# FE.net
KiCad netlist of a schematic drawn in Altium Designer
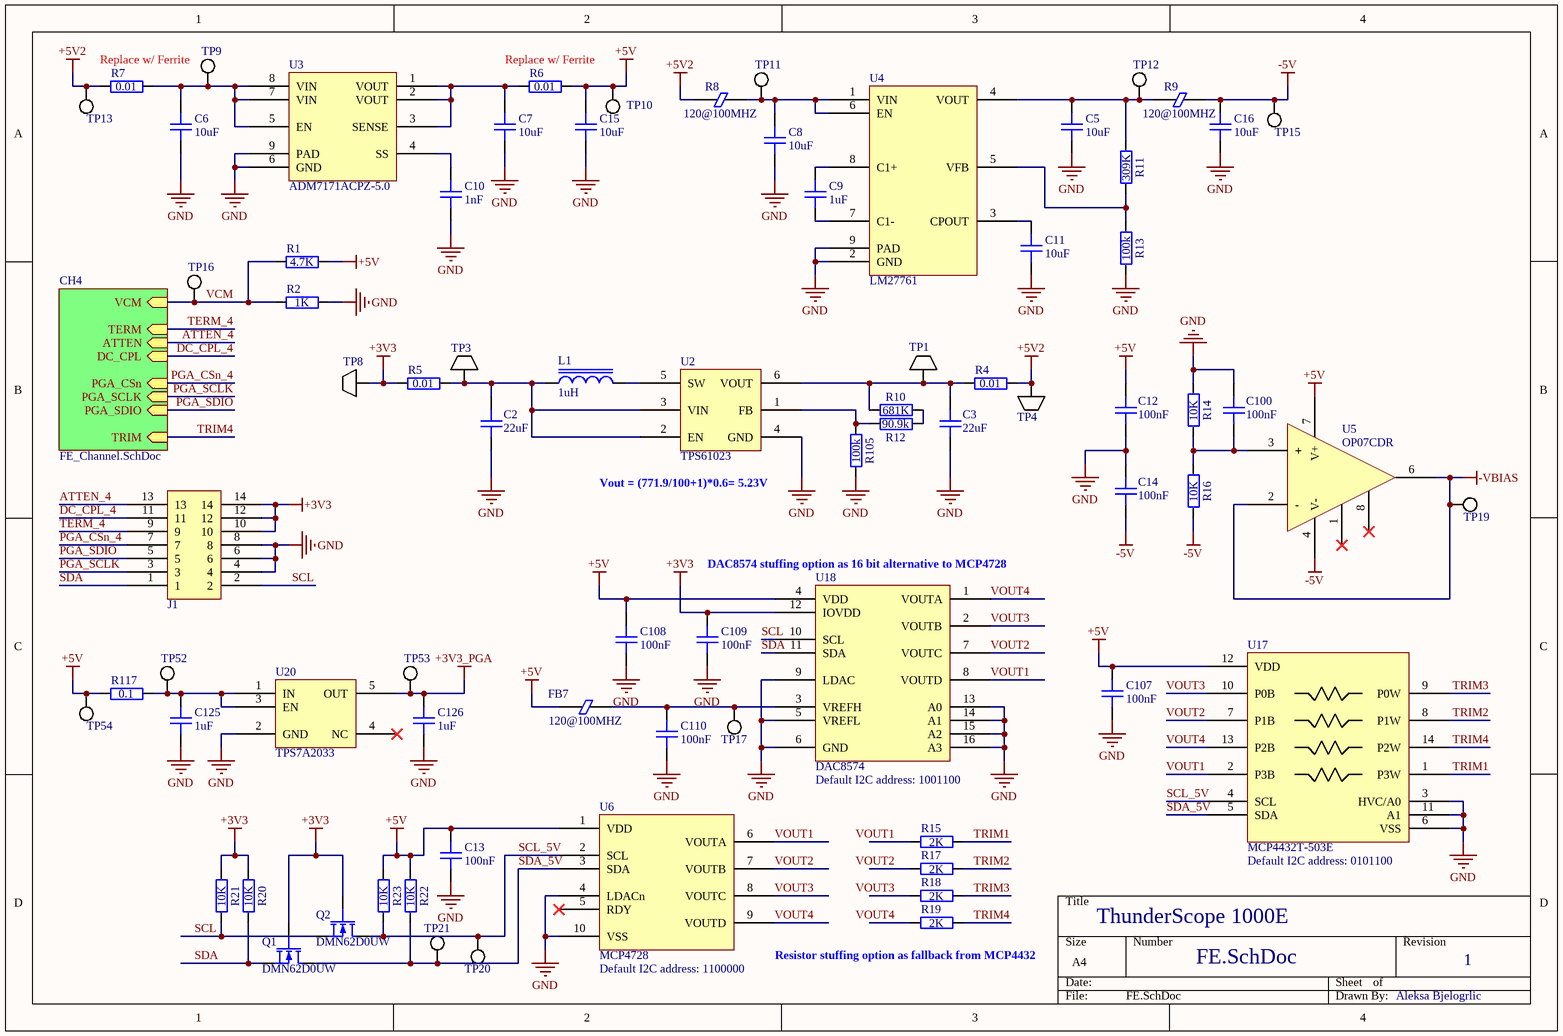
[diagram p0: FE.SchDoc]

(export (version "E")
  (design (tool "Eeschema 10.0.6"))
  (components
    (comp (ref "C2")
      (value "22uF")
      (footprint "GEN_C_0805")
      (libsource (lib "DSO") (part "CAP 22uF 25V X5R 0805"))
    )
    (comp (ref "C3")
      (value "22uF")
      (footprint "GEN_C_0805")
      (libsource (lib "DSO") (part "CAP 22uF 25V X5R 0805"))
    )
    (comp (ref "C5")
      (value "10uF")
      (footprint "GEN_C_0603")
      (libsource (lib "DSO") (part "CAP 10uF 10V X5R 0603"))
    )
    (comp (ref "C6")
      (value "10uF")
      (footprint "GEN_C_0603")
      (libsource (lib "DSO") (part "CAP 10uF 10V X5R 0603"))
    )
    (comp (ref "C7")
      (value "10uF")
      (footprint "GEN_C_0603")
      (libsource (lib "DSO") (part "CAP 10uF 10V X5R 0603"))
    )
    (comp (ref "C8")
      (value "10uF")
      (footprint "GEN_C_0603")
      (libsource (lib "DSO") (part "CAP 10uF 10V X5R 0603"))
    )
    (comp (ref "C9")
      (value "1uF")
      (footprint "GEN_C_0402")
      (libsource (lib "DSO") (part "CAP 1uF 25V X5R 0402"))
    )
    (comp (ref "C10")
      (value "1nF")
      (footprint "GEN_C_0402")
      (libsource (lib "DSO") (part "CAP 1nF 50V C0G 0402"))
    )
    (comp (ref "C11")
      (value "10uF")
      (footprint "GEN_C_0603")
      (libsource (lib "DSO") (part "CAP 10uF 10V X5R 0603"))
    )
    (comp (ref "C12")
      (value "100nF")
      (footprint "GEN_C_0402")
      (libsource (lib "DSO") (part "CAP 100nF 16V X7R 0402"))
    )
    (comp (ref "C13")
      (value "100nF")
      (footprint "GEN_C_0402")
      (libsource (lib "DSO") (part "CAP 100nF 16V X7R 0402"))
    )
    (comp (ref "C14")
      (value "100nF")
      (footprint "GEN_C_0402")
      (libsource (lib "DSO") (part "CAP 100nF 16V X7R 0402"))
    )
    (comp (ref "C15")
      (value "10uF")
      (footprint "GEN_C_0603")
      (libsource (lib "DSO") (part "CAP 10uF 10V X5R 0603"))
    )
    (comp (ref "C16")
      (value "10uF")
      (footprint "GEN_C_0603")
      (libsource (lib "DSO") (part "CAP 10uF 10V X5R 0603"))
    )
    (comp (ref "C100")
      (value "100nF")
      (footprint "GEN_C_0402")
      (libsource (lib "DSO") (part "CAP 100nF 16V X7R 0402"))
    )
    (comp (ref "C107")
      (value "100nF")
      (footprint "GEN_C_0402")
      (libsource (lib "DSO") (part "CAP 100nF 16V X7R 0402"))
    )
    (comp (ref "C108")
      (value "100nF")
      (footprint "GEN_C_0402")
      (libsource (lib "DSO") (part "CAP 100nF 16V X7R 0402"))
    )
    (comp (ref "C109")
      (value "100nF")
      (footprint "GEN_C_0402")
      (libsource (lib "DSO") (part "CAP 100nF 16V X7R 0402"))
    )
    (comp (ref "C110")
      (value "100nF")
      (footprint "GEN_C_0402")
      (libsource (lib "DSO") (part "CAP 100nF 16V X7R 0402"))
    )
    (comp (ref "C125")
      (value "1uF")
      (footprint "GEN_C_0402")
      (libsource (lib "DSO") (part "CAP 1uF 25V X5R 0402"))
    )
    (comp (ref "C126")
      (value "1uF")
      (footprint "GEN_C_0402")
      (libsource (lib "DSO") (part "CAP 1uF 25V X5R 0402"))
    )
    (comp (ref "FB7")
      (value "120@100MHZ")
      (footprint "GEN_R_0402")
      (libsource (lib "DSO") (part "FERRITE BEAD 120 OHM 0402"))
    )
    (comp (ref "J1")
      (value "2.54mm 2X7 Pin TH")
      (footprint "GEN_2.54mm_2X7_Pin_TH_RA")
      (libsource (lib "DSO") (part "CONN 2.54mm 2X7 Pin TH RA"))
    )
    (comp (ref "L1")
      (value "1uH")
      (footprint "GEN_L_1210")
      (libsource (lib "DSO") (part "IND 1uH 3.1A 45 MOHM 1210"))
    )
    (comp (ref "Q1")
      (value "DMN62D0UW")
      (footprint "GEN_SOT_323")
      (libsource (lib "DSO") (part "NMOS DMN62D0UW"))
    )
    (comp (ref "Q2")
      (value "DMN62D0UW")
      (footprint "GEN_SOT_323")
      (libsource (lib "DSO") (part "NMOS DMN62D0UW"))
    )
    (comp (ref "R1")
      (value "4.7K")
      (footprint "GEN_R_0402")
      (fields
        (field (name "TOLERANCE") "1%")
        (field (name "MANUFACTURER") "Panasonic")
        (field (name "MANUFACTURER PART NUMBER") "ERJ-2RKF4701X")
      )
      (libsource (lib "DSO") (part "RES 4.7K OHM 1% 1/10W 0402"))
    )
    (comp (ref "R2")
      (value "1K")
      (footprint "GEN_R_0402")
      (fields
        (field (name "TOLERANCE") "1%")
        (field (name "MANUFACTURER") "Yageo")
        (field (name "HOUSE PART NUMBER") "R-1K-0402-1%-001")
      )
      (libsource (lib "DSO") (part "RES 1K OHM 1% 1/10W 0402"))
    )
    (comp (ref "R4")
      (value "0.01")
      (footprint "GEN_R_0603")
      (fields (field (name "TOLERANCE") "1%"))
      (libsource (lib "DSO") (part "RES 0.01 OHM 1% 1/4W 0603"))
    )
    (comp (ref "R5")
      (value "0.01")
      (footprint "GEN_R_0603")
      (fields (field (name "TOLERANCE") "1%"))
      (libsource (lib "") (part "RES 0.01 OHM 1% 1/4W 0603_1"))
    )
    (comp (ref "R6")
      (value "0.01")
      (footprint "GEN_R_0603")
      (fields (field (name "TOLERANCE") "1%"))
      (libsource (lib "DSO") (part "RES 0.01 OHM 1% 1/4W 0603"))
    )
    (comp (ref "R7")
      (value "0.01")
      (footprint "GEN_R_0603")
      (fields (field (name "TOLERANCE") "1%"))
      (libsource (lib "DSO") (part "RES 0.01 OHM 1% 1/4W 0603"))
    )
    (comp (ref "R8")
      (value "120@100MHZ")
      (footprint "GEN_R_0402")
      (fields (field (name "MANUFACTURER") "Murata") (field (name "HOUSE PART NUMBER") "BLM15PX121SN1D"))
      (libsource (lib "DSO") (part "FERRITE BEAD 120 OHM 0402"))
    )
    (comp (ref "R9")
      (value "120@100MHZ")
      (footprint "GEN_R_0402")
      (fields (field (name "MANUFACTURER") "Murata") (field (name "HOUSE PART NUMBER") "BLM15PX121SN1D"))
      (libsource (lib "DSO") (part "FERRITE BEAD 120 OHM 0402"))
    )
    (comp (ref "R10")
      (value "681K")
      (footprint "GEN_R_0402")
      (fields (field (name "TOLERANCE") "1%"))
      (libsource (lib "DSO") (part "RES 681K OHM 1% 1/16W 0402"))
    )
    (comp (ref "R11")
      (value "309K")
      (footprint "GEN_R_0402")
      (fields (field (name "TOLERANCE") "1%"))
      (libsource (lib "DSO") (part "RES 309K OHM 1% 1/16W 0402"))
    )
    (comp (ref "R12")
      (value "90.9k")
      (footprint "GEN_R_0402")
      (fields (field (name "TOLERANCE") "1%"))
      (libsource (lib "DSO") (part "RES 90.9K OHM 1% 1/16W 0402"))
    )
    (comp (ref "R13")
      (value "100k")
      (footprint "GEN_R_0402")
      (fields (field (name "TOLERANCE") "1%"))
      (libsource (lib "DSO") (part "RES 100K OHM 1% 1/10W 0402"))
    )
    (comp (ref "R14")
      (value "10K")
      (footprint "GEN_R_0402")
      (fields (field (name "TOLERANCE") "1%"))
      (libsource (lib "DSO") (part "RES 10K OHM 1% 1/10W 0402"))
    )
    (comp (ref "R15")
      (value "2K")
      (footprint "GEN_R_0402")
      (fields (field (name "TOLERANCE") "1%"))
      (libsource (lib "DSO") (part "RES 2K OHM 1% 1/16W 0402"))
    )
    (comp (ref "R16")
      (value "10K")
      (footprint "GEN_R_0402")
      (fields (field (name "TOLERANCE") "1%"))
      (libsource (lib "DSO") (part "RES 10K OHM 1% 1/10W 0402"))
    )
    (comp (ref "R17")
      (value "2K")
      (footprint "GEN_R_0402")
      (fields (field (name "TOLERANCE") "1%"))
      (libsource (lib "DSO") (part "RES 2K OHM 1% 1/16W 0402"))
    )
    (comp (ref "R18")
      (value "2K")
      (footprint "GEN_R_0402")
      (fields (field (name "TOLERANCE") "1%"))
      (libsource (lib "DSO") (part "RES 2K OHM 1% 1/16W 0402"))
    )
    (comp (ref "R19")
      (value "2K")
      (footprint "GEN_R_0402")
      (fields (field (name "TOLERANCE") "1%"))
      (libsource (lib "DSO") (part "RES 2K OHM 1% 1/16W 0402"))
    )
    (comp (ref "R20")
      (value "10K")
      (footprint "GEN_R_0402")
      (fields (field (name "TOLERANCE") "1%"))
      (libsource (lib "DSO") (part "RES 10K OHM 1% 1/10W 0402"))
    )
    (comp (ref "R21")
      (value "10K")
      (footprint "GEN_R_0402")
      (fields (field (name "TOLERANCE") "1%"))
      (libsource (lib "DSO") (part "RES 10K OHM 1% 1/10W 0402"))
    )
    (comp (ref "R22")
      (value "10K")
      (footprint "GEN_R_0402")
      (fields (field (name "TOLERANCE") "1%"))
      (libsource (lib "DSO") (part "RES 10K OHM 1% 1/10W 0402"))
    )
    (comp (ref "R23")
      (value "10K")
      (footprint "GEN_R_0402")
      (fields (field (name "TOLERANCE") "1%"))
      (libsource (lib "DSO") (part "RES 10K OHM 1% 1/10W 0402"))
    )
    (comp (ref "R105")
      (value "100k")
      (footprint "GEN_R_0402")
      (fields (field (name "TOLERANCE") "1%"))
      (libsource (lib "DSO") (part "RES 100K OHM 1% 1/10W 0402"))
    )
    (comp (ref "R117")
      (value "0.1")
      (footprint "GEN_R_0402")
      (fields (field (name "TOLERANCE") "1%"))
      (libsource (lib "DSO") (part "RES 0.1 OHM 1% 1/6W 0402"))
    )
    (comp (ref "TP1") (value "5015") (footprint "KEY_5015") (libsource (lib "DSO") (part "TP KEYSTONE 5015")))
    (comp (ref "TP3") (value "5015") (footprint "KEY_5015") (libsource (lib "DSO") (part "TP KEYSTONE 5015")))
    (comp (ref "TP4") (value "5015") (footprint "KEY_5015") (libsource (lib "DSO") (part "TP KEYSTONE 5015")))
    (comp (ref "TP8") (value "5015") (footprint "KEY_5015") (libsource (lib "DSO") (part "TP KEYSTONE 5015")))
    (comp (ref "TP9") (value "PCB") (footprint "GEN_TP_PCB") (libsource (lib "DSO") (part "TP PCB 1mm")))
    (comp (ref "TP10") (value "PCB") (footprint "GEN_TP_PCB") (libsource (lib "DSO") (part "TP PCB 1mm")))
    (comp (ref "TP11") (value "PCB") (footprint "GEN_TP_PCB") (libsource (lib "DSO") (part "TP PCB 1mm")))
    (comp (ref "TP12") (value "PCB") (footprint "GEN_TP_PCB") (libsource (lib "DSO") (part "TP PCB 1mm")))
    (comp (ref "TP13") (value "PCB") (footprint "GEN_TP_PCB") (libsource (lib "DSO") (part "TP PCB 1mm")))
    (comp (ref "TP15") (value "PCB") (footprint "GEN_TP_PCB") (libsource (lib "DSO") (part "TP PCB 1mm")))
    (comp (ref "TP16") (value "PCB") (footprint "GEN_TP_PCB") (libsource (lib "DSO") (part "TP PCB 1mm")))
    (comp (ref "TP17") (value "PCB") (footprint "GEN_TP_PCB") (libsource (lib "DSO") (part "TP PCB 1mm")))
    (comp (ref "TP19") (value "PCB") (footprint "GEN_TP_PCB") (libsource (lib "DSO") (part "TP PCB 1mm")))
    (comp (ref "TP20") (value "PCB") (footprint "GEN_TP_PCB") (libsource (lib "DSO") (part "TP PCB 1mm")))
    (comp (ref "TP21") (value "PCB") (footprint "GEN_TP_PCB") (libsource (lib "DSO") (part "TP PCB 1mm")))
    (comp (ref "TP52") (value "PCB") (footprint "GEN_TP_PCB") (libsource (lib "DSO") (part "TP PCB 1mm")))
    (comp (ref "TP53") (value "PCB") (footprint "GEN_TP_PCB") (libsource (lib "DSO") (part "TP PCB 1mm")))
    (comp (ref "TP54") (value "PCB") (footprint "GEN_TP_PCB") (libsource (lib "DSO") (part "TP PCB 1mm")))
    (comp (ref "U2")
      (value "TPS61023")
      (footprint "TI_SOT563_DRL0006A")
      (libsource (lib "DSO") (part "IC BOOST TPS61023"))
    )
    (comp (ref "U3")
      (value "ADM7171ACPZ-5.0")
      (footprint "AD_DFN8_CP-8-21")
      (libsource (lib "DSO") (part "IC LDO ADM7171ACPZ-5.0"))
    )
    (comp (ref "U4")
      (value "LM27761")
      (footprint "TI_WSON8_DSG0008A")
      (libsource (lib "DSO") (part "IC CPUMP LM27761"))
    )
    (comp (ref "U5")
      (value "OP07CDR")
      (footprint "TI_SOIC8_D0008A")
      (libsource (lib "DSO") (part "IC OPAMP OP07CDR"))
    )
    (comp (ref "U6")
      (value "MCP4728")
      (footprint "MC_MSOP10_UN")
      (libsource (lib "DSO") (part "IC DAC QUAD MCP4728"))
    )
    (comp (ref "U17")
      (value "MCP4432T-503E")
      (footprint "MC_TSSOP14")
      (libsource (lib "DSO") (part "IC DIGIPOT QUAD MCP4432T-503E"))
    )
    (comp (ref "U18")
      (value "DAC8574")
      (footprint "TI_TSSOP16_PW0016A")
      (libsource (lib "DSO") (part "IC DAC QUAD DAC8574"))
    )
    (comp (ref "U20")
      (value "TPS7A2033")
      (footprint "GEN_SOT23_5_950_2900X1600X1450")
      (fields
        (field (name "MANUFACTURER") "Texas Instruments")
        (field (name "MANUFACTURER PART NUMBER") "TPS7A2033PDBVR")
      )
      (libsource (lib "DSO") (part "IC LDO TPS7A2033"))
    )
  )
  (nets
    (net (code "1") (name "+3V3") (class "Default")
      (node (ref "C109") (pin "2") (pinfunction "2_2") (pintype "passive"))
      (node (ref "J1") (pin "10") (pinfunction "10_10") (pintype "passive"))
      (node (ref "J1") (pin "12") (pinfunction "12_12") (pintype "passive"))
      (node (ref "J1") (pin "14") (pinfunction "14_14") (pintype "passive"))
      (node (ref "Q1") (pin "2") (pinfunction "G_2") (pintype "passive"))
      (node (ref "Q2") (pin "2") (pinfunction "G_2") (pintype "passive"))
      (node (ref "R20") (pin "2") (pinfunction "2_2") (pintype "passive"))
      (node (ref "R21") (pin "2") (pinfunction "2_2") (pintype "passive"))
      (node (ref "R5") (pin "2") (pinfunction "2_2") (pintype "passive"))
      (node (ref "TP8") (pin "1") (pinfunction "1_1") (pintype "passive"))
      (node (ref "U18") (pin "12") (pinfunction "IOVDD_12") (pintype "power_in"))
    )
    (net (code "2") (name "+3V3_PGA") (class "Default")
      (node (ref "C126") (pin "2") (pinfunction "2_2") (pintype "passive"))
      (node (ref "TP53") (pin "1") (pinfunction "1_1") (pintype "passive"))
      (node (ref "U20") (pin "5") (pinfunction "OUT_5") (pintype "power_in"))
    )
    (net (code "3") (name "+5V") (class "Default")
      (node (ref "C107") (pin "2") (pinfunction "2_2") (pintype "passive"))
      (node (ref "C108") (pin "2") (pinfunction "2_2") (pintype "passive"))
      (node (ref "C12") (pin "1") (pinfunction "1_1") (pintype "passive"))
      (node (ref "C13") (pin "2") (pinfunction "2_2") (pintype "passive"))
      (node (ref "C15") (pin "2") (pinfunction "2_2") (pintype "passive"))
      (node (ref "FB7") (pin "2") (pinfunction "2_2") (pintype "passive"))
      (node (ref "R1") (pin "2") (pinfunction "2_2") (pintype "passive"))
      (node (ref "R117") (pin "1") (pinfunction "1_1") (pintype "passive"))
      (node (ref "R22") (pin "2") (pinfunction "2_2") (pintype "passive"))
      (node (ref "R23") (pin "2") (pinfunction "2_2") (pintype "passive"))
      (node (ref "R6") (pin "2") (pinfunction "2_2") (pintype "passive"))
      (node (ref "TP10") (pin "1") (pinfunction "1_1") (pintype "passive"))
      (node (ref "TP54") (pin "1") (pinfunction "1_1") (pintype "passive"))
      (node (ref "U17") (pin "12") (pinfunction "VDD_12") (pintype "power_in"))
      (node (ref "U18") (pin "4") (pinfunction "VDD_4") (pintype "power_in"))
      (node (ref "U5") (pin "7") (pinfunction "V+_7") (pintype "passive"))
      (node (ref "U6") (pin "1") (pinfunction "VDD_1") (pintype "power_in"))
    )
    (net (code "4") (name "+5V2") (class "Default")
      (node (ref "R4") (pin "2") (pinfunction "2_2") (pintype "passive"))
      (node (ref "R7") (pin "1") (pinfunction "1_1") (pintype "passive"))
      (node (ref "R8") (pin "1") (pinfunction "1_1") (pintype "passive"))
      (node (ref "TP13") (pin "1") (pinfunction "1_1") (pintype "passive"))
      (node (ref "TP4") (pin "1") (pinfunction "1_1") (pintype "passive"))
    )
    (net (code "5") (name "-5V") (class "Default")
      (node (ref "C14") (pin "2") (pinfunction "2_2") (pintype "passive"))
      (node (ref "C16") (pin "2") (pinfunction "2_2") (pintype "passive"))
      (node (ref "R16") (pin "1") (pinfunction "1_1") (pintype "passive"))
      (node (ref "R9") (pin "2") (pinfunction "2_2") (pintype "passive"))
      (node (ref "TP15") (pin "1") (pinfunction "1_1") (pintype "passive"))
      (node (ref "U5") (pin "4") (pinfunction "V-_4") (pintype "passive"))
    )
    (net (code "6") (name "-VBIAS") (class "Default")
      (node (ref "TP19") (pin "1") (pinfunction "1_1") (pintype "passive"))
      (node (ref "U5") (pin "2") (pinfunction "-_2") (pintype "passive"))
      (node (ref "U5") (pin "6") (pinfunction "OUT_6") (pintype "passive"))
    )
    (net (code "7") (name "/ATTEN_4") (class "Default")
      (node (ref "J1") (pin "13") (pinfunction "13_13") (pintype "passive"))
    )
    (net (code "8") (name "/DC_CPL_4") (class "Default")
      (node (ref "J1") (pin "11") (pinfunction "11_11") (pintype "passive"))
    )
    (net (code "9") (name "/PGA_CSn_4") (class "Default")
      (node (ref "J1") (pin "7") (pinfunction "7_7") (pintype "passive"))
    )
    (net (code "10") (name "/PGA_SCLK") (class "Default")
      (node (ref "J1") (pin "3") (pinfunction "3_3") (pintype "passive"))
    )
    (net (code "11") (name "/PGA_SDIO") (class "Default")
      (node (ref "J1") (pin "5") (pinfunction "5_5") (pintype "passive"))
    )
    (net (code "12") (name "/SCL") (class "Default")
      (node (ref "J1") (pin "2") (pinfunction "2_2") (pintype "passive"))
      (node (ref "Q2") (pin "3") (pinfunction "S_3") (pintype "passive"))
      (node (ref "R21") (pin "1") (pinfunction "1_1") (pintype "passive"))
      (node (ref "U18") (pin "10") (pinfunction "SCL_10") (pintype "passive"))
    )
    (net (code "13") (name "/SCL_5V") (class "Default")
      (node (ref "Q2") (pin "1") (pinfunction "D_1") (pintype "passive"))
      (node (ref "R23") (pin "1") (pinfunction "1_1") (pintype "passive"))
      (node (ref "TP20") (pin "1") (pinfunction "1_1") (pintype "passive"))
      (node (ref "U17") (pin "4") (pinfunction "SCL_4") (pintype "passive"))
      (node (ref "U6") (pin "2") (pinfunction "SCL_2") (pintype "passive"))
    )
    (net (code "14") (name "/SDA") (class "Default")
      (node (ref "J1") (pin "1") (pinfunction "1_1") (pintype "passive"))
      (node (ref "Q1") (pin "3") (pinfunction "S_3") (pintype "passive"))
      (node (ref "R20") (pin "1") (pinfunction "1_1") (pintype "passive"))
      (node (ref "U18") (pin "11") (pinfunction "SDA_11") (pintype "passive"))
    )
    (net (code "15") (name "/SDA_5V") (class "Default")
      (node (ref "Q1") (pin "1") (pinfunction "D_1") (pintype "passive"))
      (node (ref "R22") (pin "1") (pinfunction "1_1") (pintype "passive"))
      (node (ref "TP21") (pin "1") (pinfunction "1_1") (pintype "passive"))
      (node (ref "U17") (pin "5") (pinfunction "SDA_5") (pintype "passive"))
      (node (ref "U6") (pin "3") (pinfunction "SDA_3") (pintype "passive"))
    )
    (net (code "16") (name "/TERM_4") (class "Default")
      (node (ref "J1") (pin "9") (pinfunction "9_9") (pintype "passive"))
    )
    (net (code "17") (name "/TRIM1") (class "Default")
      (node (ref "R15") (pin "1") (pinfunction "1_1") (pintype "passive"))
      (node (ref "U17") (pin "1") (pinfunction "P3W_1") (pintype "passive"))
    )
    (net (code "18") (name "/TRIM2") (class "Default")
      (node (ref "R17") (pin "1") (pinfunction "1_1") (pintype "passive"))
      (node (ref "U17") (pin "8") (pinfunction "P1W_8") (pintype "passive"))
    )
    (net (code "19") (name "/TRIM3") (class "Default")
      (node (ref "R18") (pin "1") (pinfunction "1_1") (pintype "passive"))
      (node (ref "U17") (pin "9") (pinfunction "P0W_9") (pintype "passive"))
    )
    (net (code "20") (name "/TRIM4") (class "Default")
      (node (ref "R19") (pin "1") (pinfunction "1_1") (pintype "passive"))
      (node (ref "U17") (pin "14") (pinfunction "P2W_14") (pintype "passive"))
    )
    (net (code "21") (name "/VCM") (class "Default")
      (node (ref "R1") (pin "1") (pinfunction "1_1") (pintype "passive"))
      (node (ref "R2") (pin "1") (pinfunction "1_1") (pintype "passive"))
      (node (ref "TP16") (pin "1") (pinfunction "1_1") (pintype "passive"))
    )
    (net (code "22") (name "/VOUT1") (class "Default")
      (node (ref "R15") (pin "2") (pinfunction "2_2") (pintype "passive"))
      (node (ref "U17") (pin "2") (pinfunction "P3B_2") (pintype "passive"))
      (node (ref "U18") (pin "8") (pinfunction "VOUTD_8") (pintype "passive"))
      (node (ref "U6") (pin "6") (pinfunction "VOUTA_6") (pintype "passive"))
    )
    (net (code "23") (name "/VOUT2") (class "Default")
      (node (ref "R17") (pin "2") (pinfunction "2_2") (pintype "passive"))
      (node (ref "U17") (pin "7") (pinfunction "P1B_7") (pintype "passive"))
      (node (ref "U18") (pin "7") (pinfunction "VOUTC_7") (pintype "passive"))
      (node (ref "U6") (pin "7") (pinfunction "VOUTB_7") (pintype "passive"))
    )
    (net (code "24") (name "/VOUT3") (class "Default")
      (node (ref "R18") (pin "2") (pinfunction "2_2") (pintype "passive"))
      (node (ref "U17") (pin "10") (pinfunction "P0B_10") (pintype "passive"))
      (node (ref "U18") (pin "2") (pinfunction "VOUTB_2") (pintype "passive"))
      (node (ref "U6") (pin "8") (pinfunction "VOUTC_8") (pintype "passive"))
    )
    (net (code "25") (name "/VOUT4") (class "Default")
      (node (ref "R19") (pin "2") (pinfunction "2_2") (pintype "passive"))
      (node (ref "U17") (pin "13") (pinfunction "P2B_13") (pintype "passive"))
      (node (ref "U18") (pin "1") (pinfunction "VOUTA_1") (pintype "passive"))
      (node (ref "U6") (pin "9") (pinfunction "VOUTD_9") (pintype "passive"))
    )
    (net (code "26") (name "GND") (class "Default")
      (node (ref "C10") (pin "1") (pinfunction "1_1") (pintype "passive"))
      (node (ref "C100") (pin "1") (pinfunction "1_1") (pintype "passive"))
      (node (ref "C107") (pin "1") (pinfunction "1_1") (pintype "passive"))
      (node (ref "C108") (pin "1") (pinfunction "1_1") (pintype "passive"))
      (node (ref "C109") (pin "1") (pinfunction "1_1") (pintype "passive"))
      (node (ref "C11") (pin "1") (pinfunction "1_1") (pintype "passive"))
      (node (ref "C110") (pin "1") (pinfunction "1_1") (pintype "passive"))
      (node (ref "C12") (pin "2") (pinfunction "2_2") (pintype "passive"))
      (node (ref "C125") (pin "1") (pinfunction "1_1") (pintype "passive"))
      (node (ref "C126") (pin "1") (pinfunction "1_1") (pintype "passive"))
      (node (ref "C13") (pin "1") (pinfunction "1_1") (pintype "passive"))
      (node (ref "C14") (pin "1") (pinfunction "1_1") (pintype "passive"))
      (node (ref "C15") (pin "1") (pinfunction "1_1") (pintype "passive"))
      (node (ref "C16") (pin "1") (pinfunction "1_1") (pintype "passive"))
      (node (ref "C2") (pin "1") (pinfunction "1_1") (pintype "passive"))
      (node (ref "C3") (pin "1") (pinfunction "1_1") (pintype "passive"))
      (node (ref "C5") (pin "1") (pinfunction "1_1") (pintype "passive"))
      (node (ref "C6") (pin "1") (pinfunction "1_1") (pintype "passive"))
      (node (ref "C7") (pin "1") (pinfunction "1_1") (pintype "passive"))
      (node (ref "C8") (pin "1") (pinfunction "1_1") (pintype "passive"))
      (node (ref "J1") (pin "4") (pinfunction "4_4") (pintype "passive"))
      (node (ref "J1") (pin "6") (pinfunction "6_6") (pintype "passive"))
      (node (ref "J1") (pin "8") (pinfunction "8_8") (pintype "passive"))
      (node (ref "R105") (pin "1") (pinfunction "1_1") (pintype "passive"))
      (node (ref "R13") (pin "1") (pinfunction "1_1") (pintype "passive"))
      (node (ref "R14") (pin "2") (pinfunction "2_2") (pintype "passive"))
      (node (ref "R2") (pin "2") (pinfunction "2_2") (pintype "passive"))
      (node (ref "U17") (pin "11") (pinfunction "A1_11") (pintype "passive"))
      (node (ref "U17") (pin "3") (pinfunction "HVC/A0_3") (pintype "passive"))
      (node (ref "U17") (pin "6") (pinfunction "VSS_6") (pintype "power_in"))
      (node (ref "U18") (pin "13") (pinfunction "A0_13") (pintype "passive"))
      (node (ref "U18") (pin "14") (pinfunction "A1_14") (pintype "passive"))
      (node (ref "U18") (pin "15") (pinfunction "A2_15") (pintype "passive"))
      (node (ref "U18") (pin "16") (pinfunction "A3_16") (pintype "passive"))
      (node (ref "U18") (pin "5") (pinfunction "VREFL_5") (pintype "passive"))
      (node (ref "U18") (pin "6") (pinfunction "GND_6") (pintype "power_in"))
      (node (ref "U18") (pin "9") (pinfunction "LDAC_9") (pintype "passive"))
      (node (ref "U2") (pin "4") (pinfunction "GND_4") (pintype "power_in"))
      (node (ref "U20") (pin "2") (pinfunction "GND_2") (pintype "power_in"))
      (node (ref "U3") (pin "6") (pinfunction "GND_6") (pintype "power_in"))
      (node (ref "U3") (pin "9") (pinfunction "PAD_9") (pintype "passive"))
      (node (ref "U4") (pin "2") (pinfunction "GND_2") (pintype "power_in"))
      (node (ref "U4") (pin "9") (pinfunction "PAD_9") (pintype "power_in"))
      (node (ref "U6") (pin "10") (pinfunction "VSS_10") (pintype "power_in"))
      (node (ref "U6") (pin "4") (pinfunction "LDACn_4") (pintype "passive"))
    )
    (net (code "27") (name "Net-(R10-Pad1)") (class "Default")
      (node (ref "R10") (pin "1") (pinfunction "1_1") (pintype "passive"))
      (node (ref "R12") (pin "2") (pinfunction "2_2") (pintype "passive"))
    )
    (net (code "28") (name "Net-(U2-EN)") (class "Default")
      (node (ref "C2") (pin "2") (pinfunction "2_2") (pintype "passive"))
      (node (ref "L1") (pin "1") (pinfunction "1_1") (pintype "passive"))
      (node (ref "R5") (pin "1") (pinfunction "1_1") (pintype "passive"))
      (node (ref "TP3") (pin "1") (pinfunction "1_1") (pintype "passive"))
      (node (ref "U2") (pin "2") (pinfunction "EN_2") (pintype "passive"))
      (node (ref "U2") (pin "3") (pinfunction "VIN_3") (pintype "power_in"))
    )
    (net (code "29") (name "Net-(U2-FB)") (class "Default")
      (node (ref "R105") (pin "2") (pinfunction "2_2") (pintype "passive"))
      (node (ref "R12") (pin "1") (pinfunction "1_1") (pintype "passive"))
      (node (ref "U2") (pin "1") (pinfunction "FB_1") (pintype "passive"))
    )
    (net (code "30") (name "Net-(U2-SW)") (class "Default")
      (node (ref "L1") (pin "2") (pinfunction "2_2") (pintype "passive"))
      (node (ref "U2") (pin "5") (pinfunction "SW_5") (pintype "passive"))
    )
    (net (code "31") (name "Net-(U2-VOUT)") (class "Default")
      (node (ref "C3") (pin "2") (pinfunction "2_2") (pintype "passive"))
      (node (ref "R10") (pin "2") (pinfunction "2_2") (pintype "passive"))
      (node (ref "R4") (pin "1") (pinfunction "1_1") (pintype "passive"))
      (node (ref "TP1") (pin "1") (pinfunction "1_1") (pintype "passive"))
      (node (ref "U2") (pin "6") (pinfunction "VOUT_6") (pintype "passive"))
    )
    (net (code "32") (name "Net-(U3-EN)") (class "Default")
      (node (ref "C6") (pin "2") (pinfunction "2_2") (pintype "passive"))
      (node (ref "R7") (pin "2") (pinfunction "2_2") (pintype "passive"))
      (node (ref "TP9") (pin "1") (pinfunction "1_1") (pintype "passive"))
      (node (ref "U3") (pin "5") (pinfunction "EN_5") (pintype "passive"))
      (node (ref "U3") (pin "7") (pinfunction "VIN_7") (pintype "power_in"))
      (node (ref "U3") (pin "8") (pinfunction "VIN_8") (pintype "power_in"))
    )
    (net (code "33") (name "Net-(U3-SENSE)") (class "Default")
      (node (ref "C7") (pin "2") (pinfunction "2_2") (pintype "passive"))
      (node (ref "R6") (pin "1") (pinfunction "1_1") (pintype "passive"))
      (node (ref "U3") (pin "1") (pinfunction "VOUT_1") (pintype "power_in"))
      (node (ref "U3") (pin "2") (pinfunction "VOUT_2") (pintype "power_in"))
      (node (ref "U3") (pin "3") (pinfunction "SENSE_3") (pintype "passive"))
    )
    (net (code "34") (name "Net-(U3-SS)") (class "Default")
      (node (ref "C10") (pin "2") (pinfunction "2_2") (pintype "passive"))
      (node (ref "U3") (pin "4") (pinfunction "SS_4") (pintype "passive"))
    )
    (net (code "35") (name "Net-(U4-C1+)") (class "Default")
      (node (ref "C9") (pin "2") (pinfunction "2_2") (pintype "passive"))
      (node (ref "U4") (pin "8") (pinfunction "C1+_8") (pintype "passive"))
    )
    (net (code "36") (name "Net-(U4-C1-)") (class "Default")
      (node (ref "C9") (pin "1") (pinfunction "1_1") (pintype "passive"))
      (node (ref "U4") (pin "7") (pinfunction "C1-_7") (pintype "passive"))
    )
    (net (code "37") (name "Net-(U4-CPOUT)") (class "Default")
      (node (ref "C11") (pin "2") (pinfunction "2_2") (pintype "passive"))
      (node (ref "U4") (pin "3") (pinfunction "CPOUT_3") (pintype "passive"))
    )
    (net (code "38") (name "Net-(U4-EN)") (class "Default")
      (node (ref "C8") (pin "2") (pinfunction "2_2") (pintype "passive"))
      (node (ref "R8") (pin "2") (pinfunction "2_2") (pintype "passive"))
      (node (ref "TP11") (pin "1") (pinfunction "1_1") (pintype "passive"))
      (node (ref "U4") (pin "1") (pinfunction "VIN_1") (pintype "power_in"))
      (node (ref "U4") (pin "6") (pinfunction "EN_6") (pintype "passive"))
    )
    (net (code "39") (name "Net-(U4-VFB)") (class "Default")
      (node (ref "R11") (pin "1") (pinfunction "1_1") (pintype "passive"))
      (node (ref "R13") (pin "2") (pinfunction "2_2") (pintype "passive"))
      (node (ref "U4") (pin "5") (pinfunction "VFB_5") (pintype "passive"))
    )
    (net (code "40") (name "Net-(U4-VOUT)") (class "Default")
      (node (ref "C5") (pin "2") (pinfunction "2_2") (pintype "passive"))
      (node (ref "R11") (pin "2") (pinfunction "2_2") (pintype "passive"))
      (node (ref "R9") (pin "1") (pinfunction "1_1") (pintype "passive"))
      (node (ref "TP12") (pin "1") (pinfunction "1_1") (pintype "passive"))
      (node (ref "U4") (pin "4") (pinfunction "VOUT_4") (pintype "power_in"))
    )
    (net (code "41") (name "Net-(U5-+)") (class "Default")
      (node (ref "C100") (pin "2") (pinfunction "2_2") (pintype "passive"))
      (node (ref "R14") (pin "1") (pinfunction "1_1") (pintype "passive"))
      (node (ref "R16") (pin "2") (pinfunction "2_2") (pintype "passive"))
      (node (ref "U5") (pin "3") (pinfunction "+_3") (pintype "passive"))
    )
    (net (code "42") (name "Net-(U18-VREFH)") (class "Default")
      (node (ref "C110") (pin "2") (pinfunction "2_2") (pintype "passive"))
      (node (ref "FB7") (pin "1") (pinfunction "1_1") (pintype "passive"))
      (node (ref "TP17") (pin "1") (pinfunction "1_1") (pintype "passive"))
      (node (ref "U18") (pin "3") (pinfunction "VREFH_3") (pintype "passive"))
    )
    (net (code "43") (name "Net-(U20-EN)") (class "Default")
      (node (ref "C125") (pin "2") (pinfunction "2_2") (pintype "passive"))
      (node (ref "R117") (pin "2") (pinfunction "2_2") (pintype "passive"))
      (node (ref "TP52") (pin "1") (pinfunction "1_1") (pintype "passive"))
      (node (ref "U20") (pin "1") (pinfunction "IN_1") (pintype "power_in"))
      (node (ref "U20") (pin "3") (pinfunction "EN_3") (pintype "passive"))
    )
    (net (code "44") (name "unconnected-(U5-N1-Pad1)") (class "Default")
      (node (ref "U5") (pin "1") (pinfunction "N1_1") (pintype "passive+no_connect"))
    )
    (net (code "45") (name "unconnected-(U5-N2-Pad8)") (class "Default")
      (node (ref "U5") (pin "8") (pinfunction "N2_8") (pintype "passive+no_connect"))
    )
    (net (code "46") (name "unconnected-(U6-RDY-Pad5)") (class "Default")
      (node (ref "U6") (pin "5") (pinfunction "RDY_5") (pintype "passive+no_connect"))
    )
    (net (code "47") (name "unconnected-(U20-NC-Pad4)") (class "Default")
      (node (ref "U20") (pin "4") (pinfunction "NC_4") (pintype "passive+no_connect"))
    )
  )
)
